# FotoMindARShield.net
KiCad netlist of a schematic drawn in EAGLE
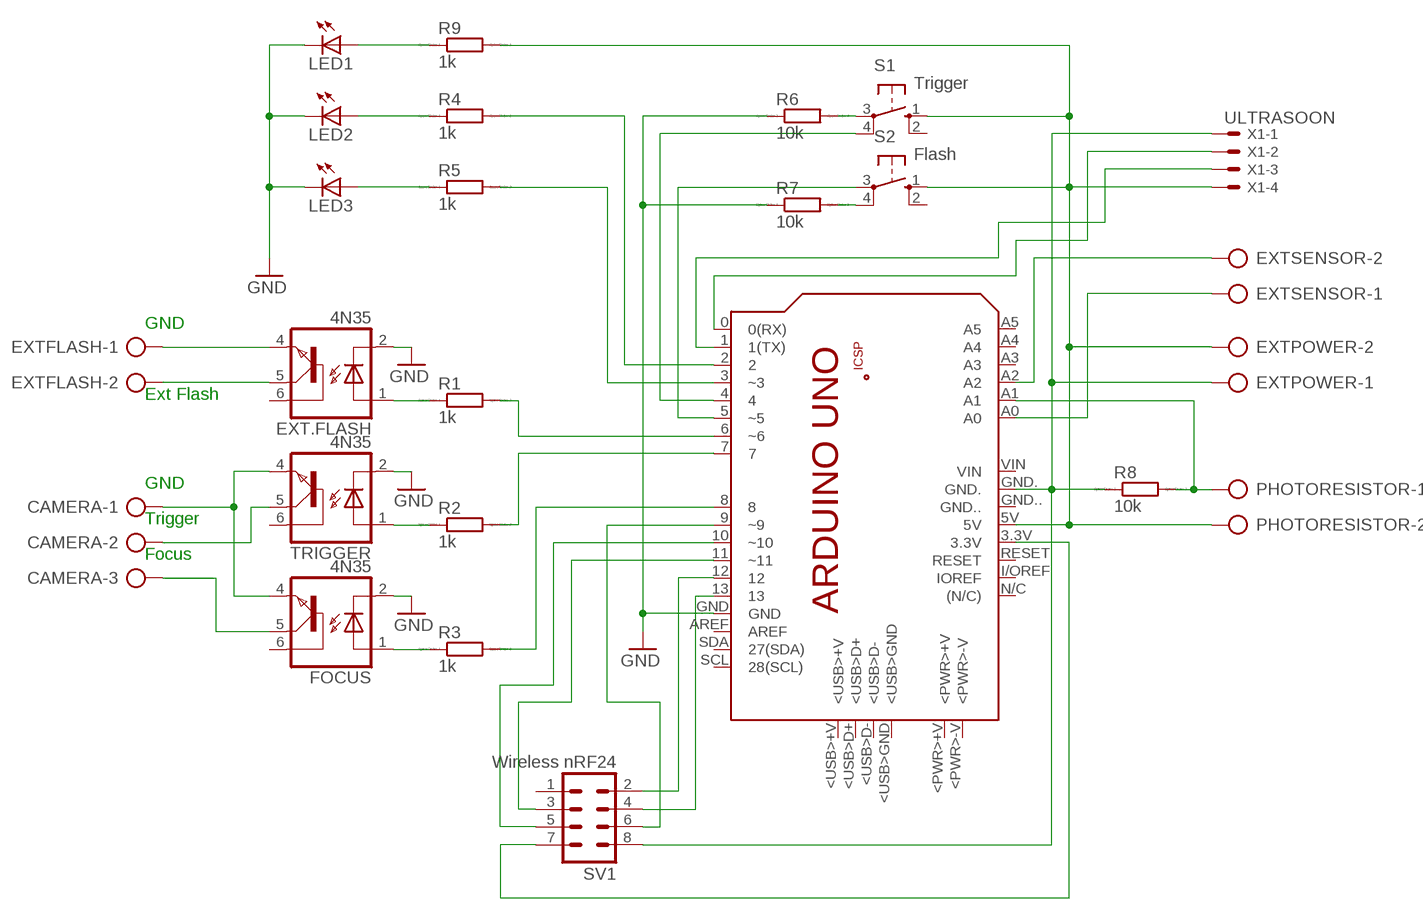
[diagram p0: schematic, sheet 1]

(export (version "E")
  (design (tool "Eeschema 10.0.6"))
  (components
    (comp (ref "CAMERA")
      (value "AK300/3")
      (footprint "eagle-import:AK300_3")
      (libsource (lib "eagle-import") (part "AK300/3"))
    )
    (comp (ref "EXT.FLASH")
      (value "4N35")
      (footprint "eagle-import:DIL06")
      (fields (field (name "MF") "FAIRCHILD SEMICONDUCTOR"))
      (libsource (lib "eagle-import") (part "4N35"))
    )
    (comp (ref "EXTFLASH")
      (value "AK300/2")
      (footprint "eagle-import:AK300_2")
      (libsource (lib "eagle-import") (part "AK300/2"))
    )
    (comp (ref "EXTPOWER")
      (value "AK300/2")
      (footprint "eagle-import:AK300_2")
      (fields (field (name "OC_FARNELL") "unknown") (field (name "OC_NEWARK") "unknown"))
      (libsource (lib "eagle-import") (part "AK300/2"))
    )
    (comp (ref "EXTSENSOR")
      (value "AK300/2")
      (footprint "eagle-import:AK300_2")
      (fields (field (name "OC_FARNELL") "unknown") (field (name "OC_NEWARK") "unknown"))
      (libsource (lib "eagle-import") (part "AK300/2"))
    )
    (comp (ref "FOCUS")
      (value "4N35")
      (footprint "eagle-import:DIL06")
      (fields (field (name "MF") "FAIRCHILD SEMICONDUCTOR"))
      (libsource (lib "eagle-import") (part "4N35"))
    )
    (comp (ref "LED1")
      (value "LED3MM")
      (footprint "eagle-import:LED3MM")
      (libsource (lib "eagle-import") (part "LED3MM"))
    )
    (comp (ref "LED2")
      (value "LED3MM")
      (footprint "eagle-import:LED3MM")
      (libsource (lib "eagle-import") (part "LED3MM"))
    )
    (comp (ref "LED3")
      (value "LED3MM")
      (footprint "eagle-import:LED3MM")
      (libsource (lib "eagle-import") (part "LED3MM"))
    )
    (comp (ref "PCB1")
      (value "ARDUINO_UNO")
      (footprint "eagle-import:ARDUINO_UNO")
      (libsource (lib "eagle-import") (part "ARDUINO_UNO"))
    )
    (comp (ref "PHOTORESISTOR")
      (value "AK300/2")
      (footprint "eagle-import:AK300_2")
      (libsource (lib "eagle-import") (part "AK300/2"))
    )
    (comp (ref "R1")
      (value "1k")
      (footprint "eagle-import:0204_7")
      (libsource (lib "eagle-import") (part "R0204/7"))
    )
    (comp (ref "R2")
      (value "1k")
      (footprint "eagle-import:0204_7")
      (libsource (lib "eagle-import") (part "R0204/7"))
    )
    (comp (ref "R3")
      (value "1k")
      (footprint "eagle-import:0204_7")
      (libsource (lib "eagle-import") (part "R0204/7"))
    )
    (comp (ref "R4")
      (value "1k")
      (footprint "eagle-import:0204_7")
      (libsource (lib "eagle-import") (part "R0204/7"))
    )
    (comp (ref "R5")
      (value "1k")
      (footprint "eagle-import:0204_7")
      (libsource (lib "eagle-import") (part "R0204/7"))
    )
    (comp (ref "R6")
      (value "10k")
      (footprint "eagle-import:0204_7")
      (libsource (lib "eagle-import") (part "R0204/7"))
    )
    (comp (ref "R7")
      (value "10k")
      (footprint "eagle-import:0204_7")
      (libsource (lib "eagle-import") (part "R0204/7"))
    )
    (comp (ref "R8")
      (value "10k")
      (footprint "eagle-import:0204_7")
      (libsource (lib "eagle-import") (part "R0204/7"))
    )
    (comp (ref "R9")
      (value "1k")
      (footprint "eagle-import:0204_7")
      (libsource (lib "eagle-import") (part "R0204/7"))
    )
    (comp (ref "S1")
      (value "Trigger")
      (footprint "eagle-import:B3F-10XX")
      (fields (field (name "MPN") "B3F-1000"))
      (libsource (lib "eagle-import") (part "10-XX"))
    )
    (comp (ref "S2")
      (value "Flash")
      (footprint "eagle-import:B3F-10XX")
      (fields (field (name "MPN") "B3F-1000"))
      (libsource (lib "eagle-import") (part "10-XX"))
    )
    (comp (ref "SV1")
      (value "Wireless nRF24")
      (footprint "eagle-import:MA04-2")
      (libsource (lib "eagle-import") (part "MA04-2"))
    )
    (comp (ref "TRIGGER")
      (value "4N35")
      (footprint "eagle-import:DIL06")
      (fields (field (name "MF") "FAIRCHILD SEMICONDUCTOR"))
      (libsource (lib "eagle-import") (part "4N35"))
    )
    (comp (ref "X1")
      (value "ULTRASOON")
      (footprint "eagle-import:22-23-2041")
      (fields (field (name "MF") "MOLEX") (field (name "MPN") "22-23-2041"))
      (libsource (lib "eagle-import") (part "22-23-2041"))
    )
  )
  (nets
    (net (code "1") (name "GND") (class "Default")
      (node (ref "EXT.FLASH") (pin "2") (pinfunction "C_2") (pintype "passive"))
      (node (ref "FOCUS") (pin "2") (pinfunction "C_2") (pintype "passive"))
      (node (ref "LED1") (pin "K") (pinfunction "C_K") (pintype "passive"))
      (node (ref "LED2") (pin "K") (pinfunction "C_K") (pintype "passive"))
      (node (ref "LED3") (pin "K") (pinfunction "C_K") (pintype "passive"))
      (node (ref "PCB1") (pin "GND") (pinfunction "GND_GND") (pintype "bidirectional"))
      (node (ref "R6") (pin "1") (pinfunction "1_1") (pintype "passive"))
      (node (ref "R7") (pin "1") (pinfunction "1_1") (pintype "passive"))
      (node (ref "TRIGGER") (pin "2") (pinfunction "C_2") (pintype "passive"))
    )
    (net (code "2") (name "Net-(CAMERAA-KL)") (class "Default")
      (node (ref "CAMERA") (pin "1") (pinfunction "KL_1") (pintype "passive"))
      (node (ref "FOCUS") (pin "4") (pinfunction "EMI_4") (pintype "passive"))
      (node (ref "TRIGGER") (pin "4") (pinfunction "EMI_4") (pintype "passive"))
    )
    (net (code "3") (name "Net-(CAMERAB-KL)") (class "Default")
      (node (ref "CAMERA") (pin "2") (pinfunction "KL_2") (pintype "passive"))
      (node (ref "TRIGGER") (pin "5") (pinfunction "COL_5") (pintype "passive"))
    )
    (net (code "4") (name "Net-(CAMERAC-KL)") (class "Default")
      (node (ref "CAMERA") (pin "3") (pinfunction "KL_3") (pintype "passive"))
      (node (ref "FOCUS") (pin "5") (pinfunction "COL_5") (pintype "passive"))
    )
    (net (code "5") (name "Net-(EXT.FLASH-A)") (class "Default")
      (node (ref "EXT.FLASH") (pin "1") (pinfunction "A_1") (pintype "passive"))
      (node (ref "R1") (pin "1") (pinfunction "1_1") (pintype "passive"))
    )
    (net (code "6") (name "Net-(EXT.FLASH-COL)") (class "Default")
      (node (ref "EXT.FLASH") (pin "5") (pinfunction "COL_5") (pintype "passive"))
      (node (ref "EXTFLASH") (pin "2") (pinfunction "KL_2") (pintype "passive"))
    )
    (net (code "7") (name "Net-(EXT.FLASH-EMI)") (class "Default")
      (node (ref "EXT.FLASH") (pin "4") (pinfunction "EMI_4") (pintype "passive"))
      (node (ref "EXTFLASH") (pin "1") (pinfunction "KL_1") (pintype "passive"))
    )
    (net (code "8") (name "Net-(EXTPOWERA-KL)") (class "Default")
      (node (ref "EXTPOWER") (pin "1") (pinfunction "KL_1") (pintype "passive"))
      (node (ref "PCB1") (pin "GND.") (pinfunction "GND._GND.") (pintype "bidirectional"))
      (node (ref "R8") (pin "1") (pinfunction "1_1") (pintype "passive"))
      (node (ref "SV1") (pin "8") (pinfunction "8_8") (pintype "passive"))
      (node (ref "X1") (pin "1") (pinfunction "S_1") (pintype "passive"))
    )
    (net (code "9") (name "Net-(EXTPOWERB-KL)") (class "Default")
      (node (ref "EXTPOWER") (pin "2") (pinfunction "KL_2") (pintype "passive"))
      (node (ref "PCB1") (pin "5V") (pinfunction "5V_5V") (pintype "bidirectional"))
      (node (ref "PHOTORESISTOR") (pin "2") (pinfunction "KL_2") (pintype "passive"))
      (node (ref "R9") (pin "2") (pinfunction "2_2") (pintype "passive"))
      (node (ref "S1") (pin "1") (pinfunction "S_1") (pintype "passive"))
      (node (ref "S2") (pin "1") (pinfunction "S_1") (pintype "passive"))
      (node (ref "X1") (pin "4") (pinfunction "S_4") (pintype "passive"))
    )
    (net (code "10") (name "Net-(EXTSENSORA-KL)") (class "Default")
      (node (ref "EXTSENSOR") (pin "1") (pinfunction "KL_1") (pintype "passive"))
      (node (ref "PCB1") (pin "A0") (pinfunction "A0_A0") (pintype "bidirectional"))
    )
    (net (code "11") (name "Net-(EXTSENSORB-KL)") (class "Default")
      (node (ref "EXTSENSOR") (pin "2") (pinfunction "KL_2") (pintype "passive"))
      (node (ref "PCB1") (pin "A2") (pinfunction "A2_A2") (pintype "bidirectional"))
    )
    (net (code "12") (name "Net-(FOCUS-A)") (class "Default")
      (node (ref "FOCUS") (pin "1") (pinfunction "A_1") (pintype "passive"))
      (node (ref "R3") (pin "1") (pinfunction "1_1") (pintype "passive"))
    )
    (net (code "13") (name "Net-(LED1-PadA)") (class "Default")
      (node (ref "LED1") (pin "A") (pinfunction "A_A") (pintype "passive"))
      (node (ref "R9") (pin "1") (pinfunction "1_1") (pintype "passive"))
    )
    (net (code "14") (name "Net-(LED2-PadA)") (class "Default")
      (node (ref "LED2") (pin "A") (pinfunction "A_A") (pintype "passive"))
      (node (ref "R4") (pin "1") (pinfunction "1_1") (pintype "passive"))
    )
    (net (code "15") (name "Net-(LED3-PadA)") (class "Default")
      (node (ref "LED3") (pin "A") (pinfunction "A_A") (pintype "passive"))
      (node (ref "R5") (pin "1") (pinfunction "1_1") (pintype "passive"))
    )
    (net (code "16") (name "Net-(PCB1-0(RX))") (class "Default")
      (node (ref "PCB1") (pin "0") (pinfunction "0(RX)_0") (pintype "bidirectional"))
      (node (ref "X1") (pin "2") (pinfunction "S_2") (pintype "passive"))
    )
    (net (code "17") (name "Net-(PCB1-1(TX))") (class "Default")
      (node (ref "PCB1") (pin "1") (pinfunction "1(TX)_1") (pintype "bidirectional"))
      (node (ref "X1") (pin "3") (pinfunction "S_3") (pintype "passive"))
    )
    (net (code "18") (name "Net-(PCB1-Pad2)") (class "Default")
      (node (ref "PCB1") (pin "2") (pinfunction "2_2") (pintype "bidirectional"))
      (node (ref "R4") (pin "2") (pinfunction "2_2") (pintype "passive"))
    )
    (net (code "19") (name "Net-(PCB1-Pad3.3V)") (class "Default")
      (node (ref "PCB1") (pin "3.3V") (pinfunction "3.3V_3.3V") (pintype "bidirectional"))
      (node (ref "SV1") (pin "7") (pinfunction "7_7") (pintype "passive"))
    )
    (net (code "20") (name "Net-(PCB1-Pad7)") (class "Default")
      (node (ref "PCB1") (pin "7") (pinfunction "7_7") (pintype "bidirectional"))
      (node (ref "R2") (pin "2") (pinfunction "2_2") (pintype "passive"))
    )
    (net (code "21") (name "Net-(PCB1-Pad8)") (class "Default")
      (node (ref "PCB1") (pin "8") (pinfunction "8_8") (pintype "bidirectional"))
      (node (ref "R3") (pin "2") (pinfunction "2_2") (pintype "passive"))
    )
    (net (code "22") (name "Net-(PCB1-Pad12)") (class "Default")
      (node (ref "PCB1") (pin "12") (pinfunction "12_12") (pintype "bidirectional"))
      (node (ref "SV1") (pin "2") (pinfunction "2_2") (pintype "passive"))
    )
    (net (code "23") (name "Net-(PCB1-Pad13)") (class "Default")
      (node (ref "PCB1") (pin "13") (pinfunction "13_13") (pintype "bidirectional"))
      (node (ref "SV1") (pin "4") (pinfunction "4_4") (pintype "passive"))
    )
    (net (code "24") (name "Net-(PCB1-~{3})") (class "Default")
      (node (ref "PCB1") (pin "3") (pinfunction "~{3}_3") (pintype "bidirectional"))
      (node (ref "R5") (pin "2") (pinfunction "2_2") (pintype "passive"))
    )
    (net (code "25") (name "Net-(PCB1-~{5})") (class "Default")
      (node (ref "PCB1") (pin "5") (pinfunction "~{5}_5") (pintype "bidirectional"))
      (node (ref "S2") (pin "3") (pinfunction "P_3") (pintype "passive"))
    )
    (net (code "26") (name "Net-(PCB1-~{6})") (class "Default")
      (node (ref "PCB1") (pin "6") (pinfunction "~{6}_6") (pintype "bidirectional"))
      (node (ref "R1") (pin "2") (pinfunction "2_2") (pintype "passive"))
    )
    (net (code "27") (name "Net-(PCB1-~{9})") (class "Default")
      (node (ref "PCB1") (pin "9") (pinfunction "~{9}_9") (pintype "bidirectional"))
      (node (ref "SV1") (pin "6") (pinfunction "6_6") (pintype "passive"))
    )
    (net (code "28") (name "Net-(PCB1-~{10})") (class "Default")
      (node (ref "PCB1") (pin "10") (pinfunction "~{10}_10") (pintype "bidirectional"))
      (node (ref "SV1") (pin "5") (pinfunction "5_5") (pintype "passive"))
    )
    (net (code "29") (name "Net-(PCB1-~{11})") (class "Default")
      (node (ref "PCB1") (pin "11") (pinfunction "~{11}_11") (pintype "bidirectional"))
      (node (ref "SV1") (pin "3") (pinfunction "3_3") (pintype "passive"))
    )
    (net (code "30") (name "Net-(PHOTORESISTORA-KL)") (class "Default")
      (node (ref "PCB1") (pin "A1") (pinfunction "A1_A1") (pintype "bidirectional"))
      (node (ref "PHOTORESISTOR") (pin "1") (pinfunction "KL_1") (pintype "passive"))
      (node (ref "R8") (pin "2") (pinfunction "2_2") (pintype "passive"))
    )
    (net (code "31") (name "Net-(S1-P)") (class "Default")
      (node (ref "R6") (pin "2") (pinfunction "2_2") (pintype "passive"))
      (node (ref "S1") (pin "3") (pinfunction "P_3") (pintype "passive"))
    )
    (net (code "32") (name "Net-(S1-P1)") (class "Default")
      (node (ref "PCB1") (pin "4") (pinfunction "4_4") (pintype "bidirectional"))
      (node (ref "S1") (pin "4") (pinfunction "P1_4") (pintype "passive"))
    )
    (net (code "33") (name "Net-(S2-P1)") (class "Default")
      (node (ref "R7") (pin "2") (pinfunction "2_2") (pintype "passive"))
      (node (ref "S2") (pin "4") (pinfunction "P1_4") (pintype "passive"))
    )
    (net (code "34") (name "Net-(TRIGGER-A)") (class "Default")
      (node (ref "R2") (pin "1") (pinfunction "1_1") (pintype "passive"))
      (node (ref "TRIGGER") (pin "1") (pinfunction "A_1") (pintype "passive"))
    )
    (net (code "35") (name "unconnected-(EXT.FLASH-BAS-Pad6)") (class "Default")
      (node (ref "EXT.FLASH") (pin "6") (pinfunction "BAS_6") (pintype "passive"))
    )
    (net (code "36") (name "unconnected-(FOCUS-BAS-Pad6)") (class "Default")
      (node (ref "FOCUS") (pin "6") (pinfunction "BAS_6") (pintype "passive"))
    )
    (net (code "37") (name "unconnected-(PCB1-(N{slash}C)-PadN{slash}C)") (class "Default")
      (node (ref "PCB1") (pin "N/C") (pinfunction "(N/C)_N/C") (pintype "bidirectional"))
    )
    (net (code "38") (name "unconnected-(PCB1-27(SDA)-PadSDA)") (class "Default")
      (node (ref "PCB1") (pin "SDA") (pinfunction "27(SDA)_SDA") (pintype "bidirectional"))
    )
    (net (code "39") (name "unconnected-(PCB1-28(SCL)-PadSCL)") (class "Default")
      (node (ref "PCB1") (pin "SCL") (pinfunction "28(SCL)_SCL") (pintype "bidirectional"))
    )
    (net (code "40") (name "unconnected-(PCB1-IOREF-PadI{slash}OREF)") (class "Default")
      (node (ref "PCB1") (pin "I/OREF") (pinfunction "IOREF_I/OREF") (pintype "bidirectional"))
    )
    (net (code "41") (name "unconnected-(PCB1-Pad+5V)") (class "Default")
      (node (ref "PCB1") (pin "+5V") (pinfunction "+5V_+5V") (pintype "bidirectional"))
    )
    (net (code "42") (name "unconnected-(PCB1-Pad<PWR>+V)") (class "Default")
      (node (ref "PCB1") (pin "<PWR>+V") (pinfunction "<PWR>+V_<PWR>+V") (pintype "bidirectional"))
    )
    (net (code "43") (name "unconnected-(PCB1-Pad<PWR>-V)") (class "Default")
      (node (ref "PCB1") (pin "<PWR>-V") (pinfunction "<PWR>-V_<PWR>-V") (pintype "bidirectional"))
    )
    (net (code "44") (name "unconnected-(PCB1-Pad<USB>+V)") (class "Default")
      (node (ref "PCB1") (pin "<USB>+V") (pinfunction "<USB>+V_<USB>+V") (pintype "bidirectional"))
    )
    (net (code "45") (name "unconnected-(PCB1-Pad<USB>D+)") (class "Default")
      (node (ref "PCB1") (pin "<USB>D+") (pinfunction "<USB>D+_<USB>D+") (pintype "bidirectional"))
    )
    (net (code "46") (name "unconnected-(PCB1-Pad<USB>D-)") (class "Default")
      (node (ref "PCB1") (pin "<USB>D-") (pinfunction "<USB>D-_<USB>D-") (pintype "bidirectional"))
    )
    (net (code "47") (name "unconnected-(PCB1-Pad<USB>GND)") (class "Default")
      (node (ref "PCB1") (pin "<USB>GND") (pinfunction "<USB>GND_<USB>GND") (pintype "bidirectional"))
    )
    (net (code "48") (name "unconnected-(PCB1-PadA3)") (class "Default")
      (node (ref "PCB1") (pin "A3") (pinfunction "A3_A3") (pintype "bidirectional"))
    )
    (net (code "49") (name "unconnected-(PCB1-PadA4)") (class "Default")
      (node (ref "PCB1") (pin "A4") (pinfunction "A4_A4") (pintype "bidirectional"))
    )
    (net (code "50") (name "unconnected-(PCB1-PadA5)") (class "Default")
      (node (ref "PCB1") (pin "A5") (pinfunction "A5_A5") (pintype "bidirectional"))
    )
    (net (code "51") (name "unconnected-(PCB1-PadAREF)") (class "Default")
      (node (ref "PCB1") (pin "AREF") (pinfunction "AREF_AREF") (pintype "bidirectional"))
    )
    (net (code "52") (name "unconnected-(PCB1-PadGND..)") (class "Default")
      (node (ref "PCB1") (pin "GND..") (pinfunction "GND.._GND..") (pintype "bidirectional"))
    )
    (net (code "53") (name "unconnected-(PCB1-PadGND_)") (class "Default")
      (node (ref "PCB1") (pin "GND_") (pinfunction "GND__GND_") (pintype "bidirectional"))
    )
    (net (code "54") (name "unconnected-(PCB1-PadMISO)") (class "Default")
      (node (ref "PCB1") (pin "MISO") (pinfunction "MISO_MISO") (pintype "bidirectional"))
    )
    (net (code "55") (name "unconnected-(PCB1-PadMOSI)") (class "Default")
      (node (ref "PCB1") (pin "MOSI") (pinfunction "MOSI_MOSI") (pintype "bidirectional"))
    )
    (net (code "56") (name "unconnected-(PCB1-PadRESET)") (class "Default")
      (node (ref "PCB1") (pin "RESET") (pinfunction "RESET_RESET") (pintype "bidirectional"))
    )
    (net (code "57") (name "unconnected-(PCB1-PadRESET.)") (class "Default")
      (node (ref "PCB1") (pin "RESET.") (pinfunction "RESET._RESET.") (pintype "bidirectional"))
    )
    (net (code "58") (name "unconnected-(PCB1-PadSCK)") (class "Default")
      (node (ref "PCB1") (pin "SCK") (pinfunction "SCK_SCK") (pintype "bidirectional"))
    )
    (net (code "59") (name "unconnected-(PCB1-PadVIN)") (class "Default")
      (node (ref "PCB1") (pin "VIN") (pinfunction "VIN_VIN") (pintype "bidirectional"))
    )
    (net (code "60") (name "unconnected-(S1-S1-Pad2)") (class "Default")
      (node (ref "S1") (pin "2") (pinfunction "S1_2") (pintype "passive"))
    )
    (net (code "61") (name "unconnected-(S2-S1-Pad2)") (class "Default")
      (node (ref "S2") (pin "2") (pinfunction "S1_2") (pintype "passive"))
    )
    (net (code "62") (name "unconnected-(SV1-Pad1)") (class "Default")
      (node (ref "SV1") (pin "1") (pinfunction "1_1") (pintype "passive"))
    )
    (net (code "63") (name "unconnected-(TRIGGER-BAS-Pad6)") (class "Default")
      (node (ref "TRIGGER") (pin "6") (pinfunction "BAS_6") (pintype "passive"))
    )
  )
)
